# miniadsb.net
KiCad netlist of a schematic drawn in EAGLE
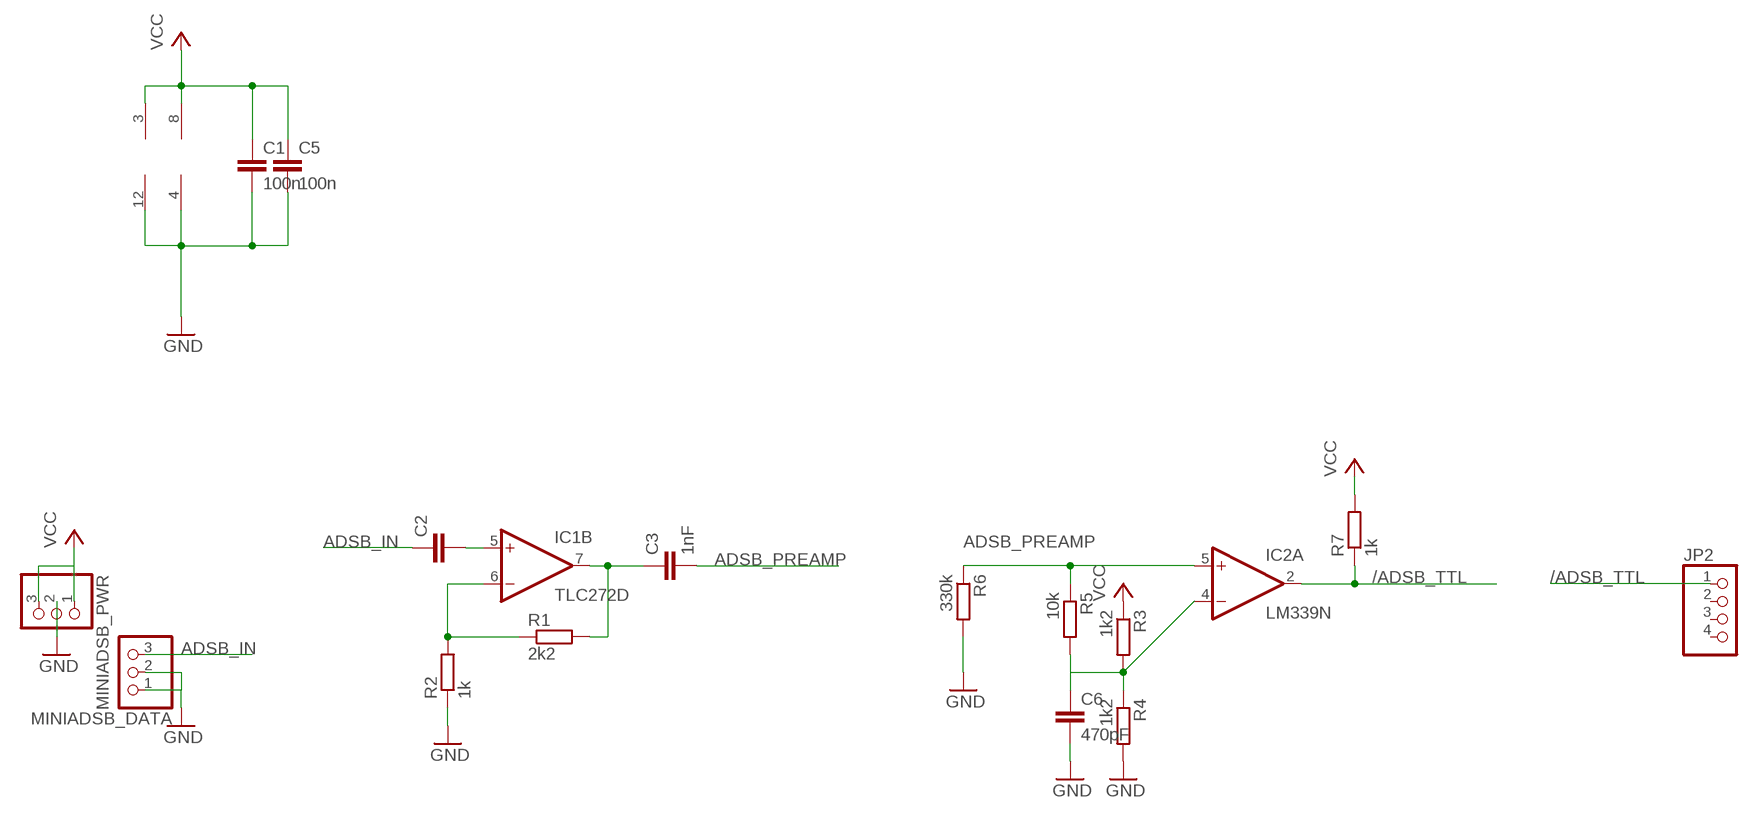
[diagram p0: schematic, sheet 1]

(export (version "E")
  (design (tool "Eeschema 10.0.6"))
  (components
    (comp (ref "C1")
      (value "100n")
      (footprint "eagle-import:C0805")
      (libsource (lib "eagle-import") (part "C-EUC0805"))
    )
    (comp (ref "C2")
      (value "C-EUC0805")
      (footprint "eagle-import:C0805")
      (libsource (lib "eagle-import") (part "C-EUC0805"))
    )
    (comp (ref "C3")
      (value "1nF")
      (footprint "eagle-import:C0805")
      (libsource (lib "eagle-import") (part "C-EUC0805"))
    )
    (comp (ref "C5")
      (value "100n")
      (footprint "eagle-import:C0805")
      (libsource (lib "eagle-import") (part "C-EUC0805"))
    )
    (comp (ref "C6")
      (value "470pF")
      (footprint "eagle-import:C0805")
      (libsource (lib "eagle-import") (part "C-EUC0805"))
    )
    (comp (ref "IC1")
      (value "TLC272D")
      (footprint "eagle-import:SO08")
      (libsource (lib "eagle-import") (part "TLC272D"))
    )
    (comp (ref "IC2")
      (value "LM339N")
      (footprint "eagle-import:DIL14")
      (libsource (lib "eagle-import") (part "LM339N"))
    )
    (comp (ref "JP2")
      (value "PINHD-1X4")
      (footprint "eagle-import:1X04")
      (libsource (lib "eagle-import") (part "PINHD-1X4"))
    )
    (comp (ref "MINIADSB_DATA")
      (value "PINHD-1X3")
      (footprint "eagle-import:1X03")
      (libsource (lib "eagle-import") (part "PINHD-1X3"))
    )
    (comp (ref "MINIADSB_PWR")
      (value "PINHD-1X3")
      (footprint "eagle-import:1X03")
      (libsource (lib "eagle-import") (part "PINHD-1X3"))
    )
    (comp (ref "R1")
      (value "2k2")
      (footprint "eagle-import:R0805")
      (libsource (lib "eagle-import") (part "resistor_R-EU_R0805"))
    )
    (comp (ref "R2")
      (value "1k")
      (footprint "eagle-import:R0805")
      (libsource (lib "eagle-import") (part "resistor_R-EU_R0805"))
    )
    (comp (ref "R3")
      (value "1k2")
      (footprint "eagle-import:R0805")
      (libsource (lib "eagle-import") (part "resistor_R-EU_R0805"))
    )
    (comp (ref "R4")
      (value "1k2")
      (footprint "eagle-import:R0805")
      (libsource (lib "eagle-import") (part "resistor_R-EU_R0805"))
    )
    (comp (ref "R5")
      (value "10k")
      (footprint "eagle-import:R0805")
      (libsource (lib "eagle-import") (part "resistor_R-EU_R0805"))
    )
    (comp (ref "R6")
      (value "330k")
      (footprint "eagle-import:R0805")
      (libsource (lib "eagle-import") (part "resistor_R-EU_R0805"))
    )
    (comp (ref "R7")
      (value "1k")
      (footprint "eagle-import:R0603")
      (libsource (lib "eagle-import") (part "R-EU_R0603"))
    )
  )
  (nets
    (net (code "1") (name "/ADSB_IN") (class "Default")
      (node (ref "C2") (pin "1") (pinfunction "1_1") (pintype "passive"))
      (node (ref "MINIADSB_DATA") (pin "3") (pinfunction "3_3") (pintype "passive"))
    )
    (net (code "2") (name "/ADSB_PREAMP") (class "Default")
      (node (ref "C3") (pin "2") (pinfunction "2_2") (pintype "passive"))
      (node (ref "IC2") (pin "5") (pinfunction "+IN_5") (pintype "input"))
      (node (ref "R5") (pin "1") (pinfunction "1_1") (pintype "passive"))
      (node (ref "R6") (pin "1") (pinfunction "1_1") (pintype "passive"))
    )
    (net (code "3") (name "/{slash}ADSB_TTL") (class "Default")
      (node (ref "IC2") (pin "2") (pinfunction "OUT_2") (pintype "open_collector"))
      (node (ref "JP2") (pin "1") (pinfunction "1_1") (pintype "passive"))
      (node (ref "R7") (pin "1") (pinfunction "1_1") (pintype "passive"))
    )
    (net (code "4") (name "GND") (class "Default")
      (node (ref "C1") (pin "2") (pinfunction "2_2") (pintype "passive"))
      (node (ref "C5") (pin "2") (pinfunction "2_2") (pintype "passive"))
      (node (ref "C6") (pin "2") (pinfunction "2_2") (pintype "passive"))
      (node (ref "IC1") (pin "4") (pinfunction "V-_4") (pintype "power_in"))
      (node (ref "IC2") (pin "12") (pinfunction "GND_12") (pintype "power_in"))
      (node (ref "MINIADSB_DATA") (pin "1") (pinfunction "1_1") (pintype "passive"))
      (node (ref "MINIADSB_DATA") (pin "2") (pinfunction "2_2") (pintype "passive"))
      (node (ref "MINIADSB_PWR") (pin "2") (pinfunction "2_2") (pintype "passive"))
      (node (ref "R2") (pin "1") (pinfunction "1_1") (pintype "passive"))
      (node (ref "R4") (pin "2") (pinfunction "2_2") (pintype "passive"))
      (node (ref "R6") (pin "2") (pinfunction "2_2") (pintype "passive"))
    )
    (net (code "5") (name "Net-(IC1B-+IN)") (class "Default")
      (node (ref "C2") (pin "2") (pinfunction "2_2") (pintype "passive"))
      (node (ref "IC1") (pin "5") (pinfunction "+IN_5") (pintype "input"))
    )
    (net (code "6") (name "Net-(IC1B--IN)") (class "Default")
      (node (ref "IC1") (pin "6") (pinfunction "-IN_6") (pintype "input"))
      (node (ref "R1") (pin "1") (pinfunction "1_1") (pintype "passive"))
      (node (ref "R2") (pin "2") (pinfunction "2_2") (pintype "passive"))
    )
    (net (code "7") (name "Net-(IC1B-OUT)") (class "Default")
      (node (ref "C3") (pin "1") (pinfunction "1_1") (pintype "passive"))
      (node (ref "IC1") (pin "7") (pinfunction "OUT_7") (pintype "output"))
      (node (ref "R1") (pin "2") (pinfunction "2_2") (pintype "passive"))
    )
    (net (code "8") (name "Net-(IC2A--IN)") (class "Default")
      (node (ref "C6") (pin "1") (pinfunction "1_1") (pintype "passive"))
      (node (ref "IC2") (pin "4") (pinfunction "-IN_4") (pintype "input"))
      (node (ref "R3") (pin "2") (pinfunction "2_2") (pintype "passive"))
      (node (ref "R4") (pin "1") (pinfunction "1_1") (pintype "passive"))
      (node (ref "R5") (pin "2") (pinfunction "2_2") (pintype "passive"))
    )
    (net (code "9") (name "VCC") (class "Default")
      (node (ref "C1") (pin "1") (pinfunction "1_1") (pintype "passive"))
      (node (ref "C5") (pin "1") (pinfunction "1_1") (pintype "passive"))
      (node (ref "IC1") (pin "8") (pinfunction "V+_8") (pintype "power_in"))
      (node (ref "IC2") (pin "3") (pinfunction "V+_3") (pintype "power_in"))
      (node (ref "MINIADSB_PWR") (pin "1") (pinfunction "1_1") (pintype "passive"))
      (node (ref "MINIADSB_PWR") (pin "3") (pinfunction "3_3") (pintype "passive"))
      (node (ref "R3") (pin "1") (pinfunction "1_1") (pintype "passive"))
      (node (ref "R7") (pin "2") (pinfunction "2_2") (pintype "passive"))
    )
    (net (code "10") (name "unconnected-(JP2-Pad2)") (class "Default")
      (node (ref "JP2") (pin "2") (pinfunction "2_2") (pintype "passive"))
    )
    (net (code "11") (name "unconnected-(JP2-Pad3)") (class "Default")
      (node (ref "JP2") (pin "3") (pinfunction "3_3") (pintype "passive"))
    )
    (net (code "12") (name "unconnected-(JP2-Pad4)") (class "Default")
      (node (ref "JP2") (pin "4") (pinfunction "4_4") (pintype "passive"))
    )
  )
)
